# 5_Motors_MCU.net
KiCad netlist of a schematic drawn in Altium Designer
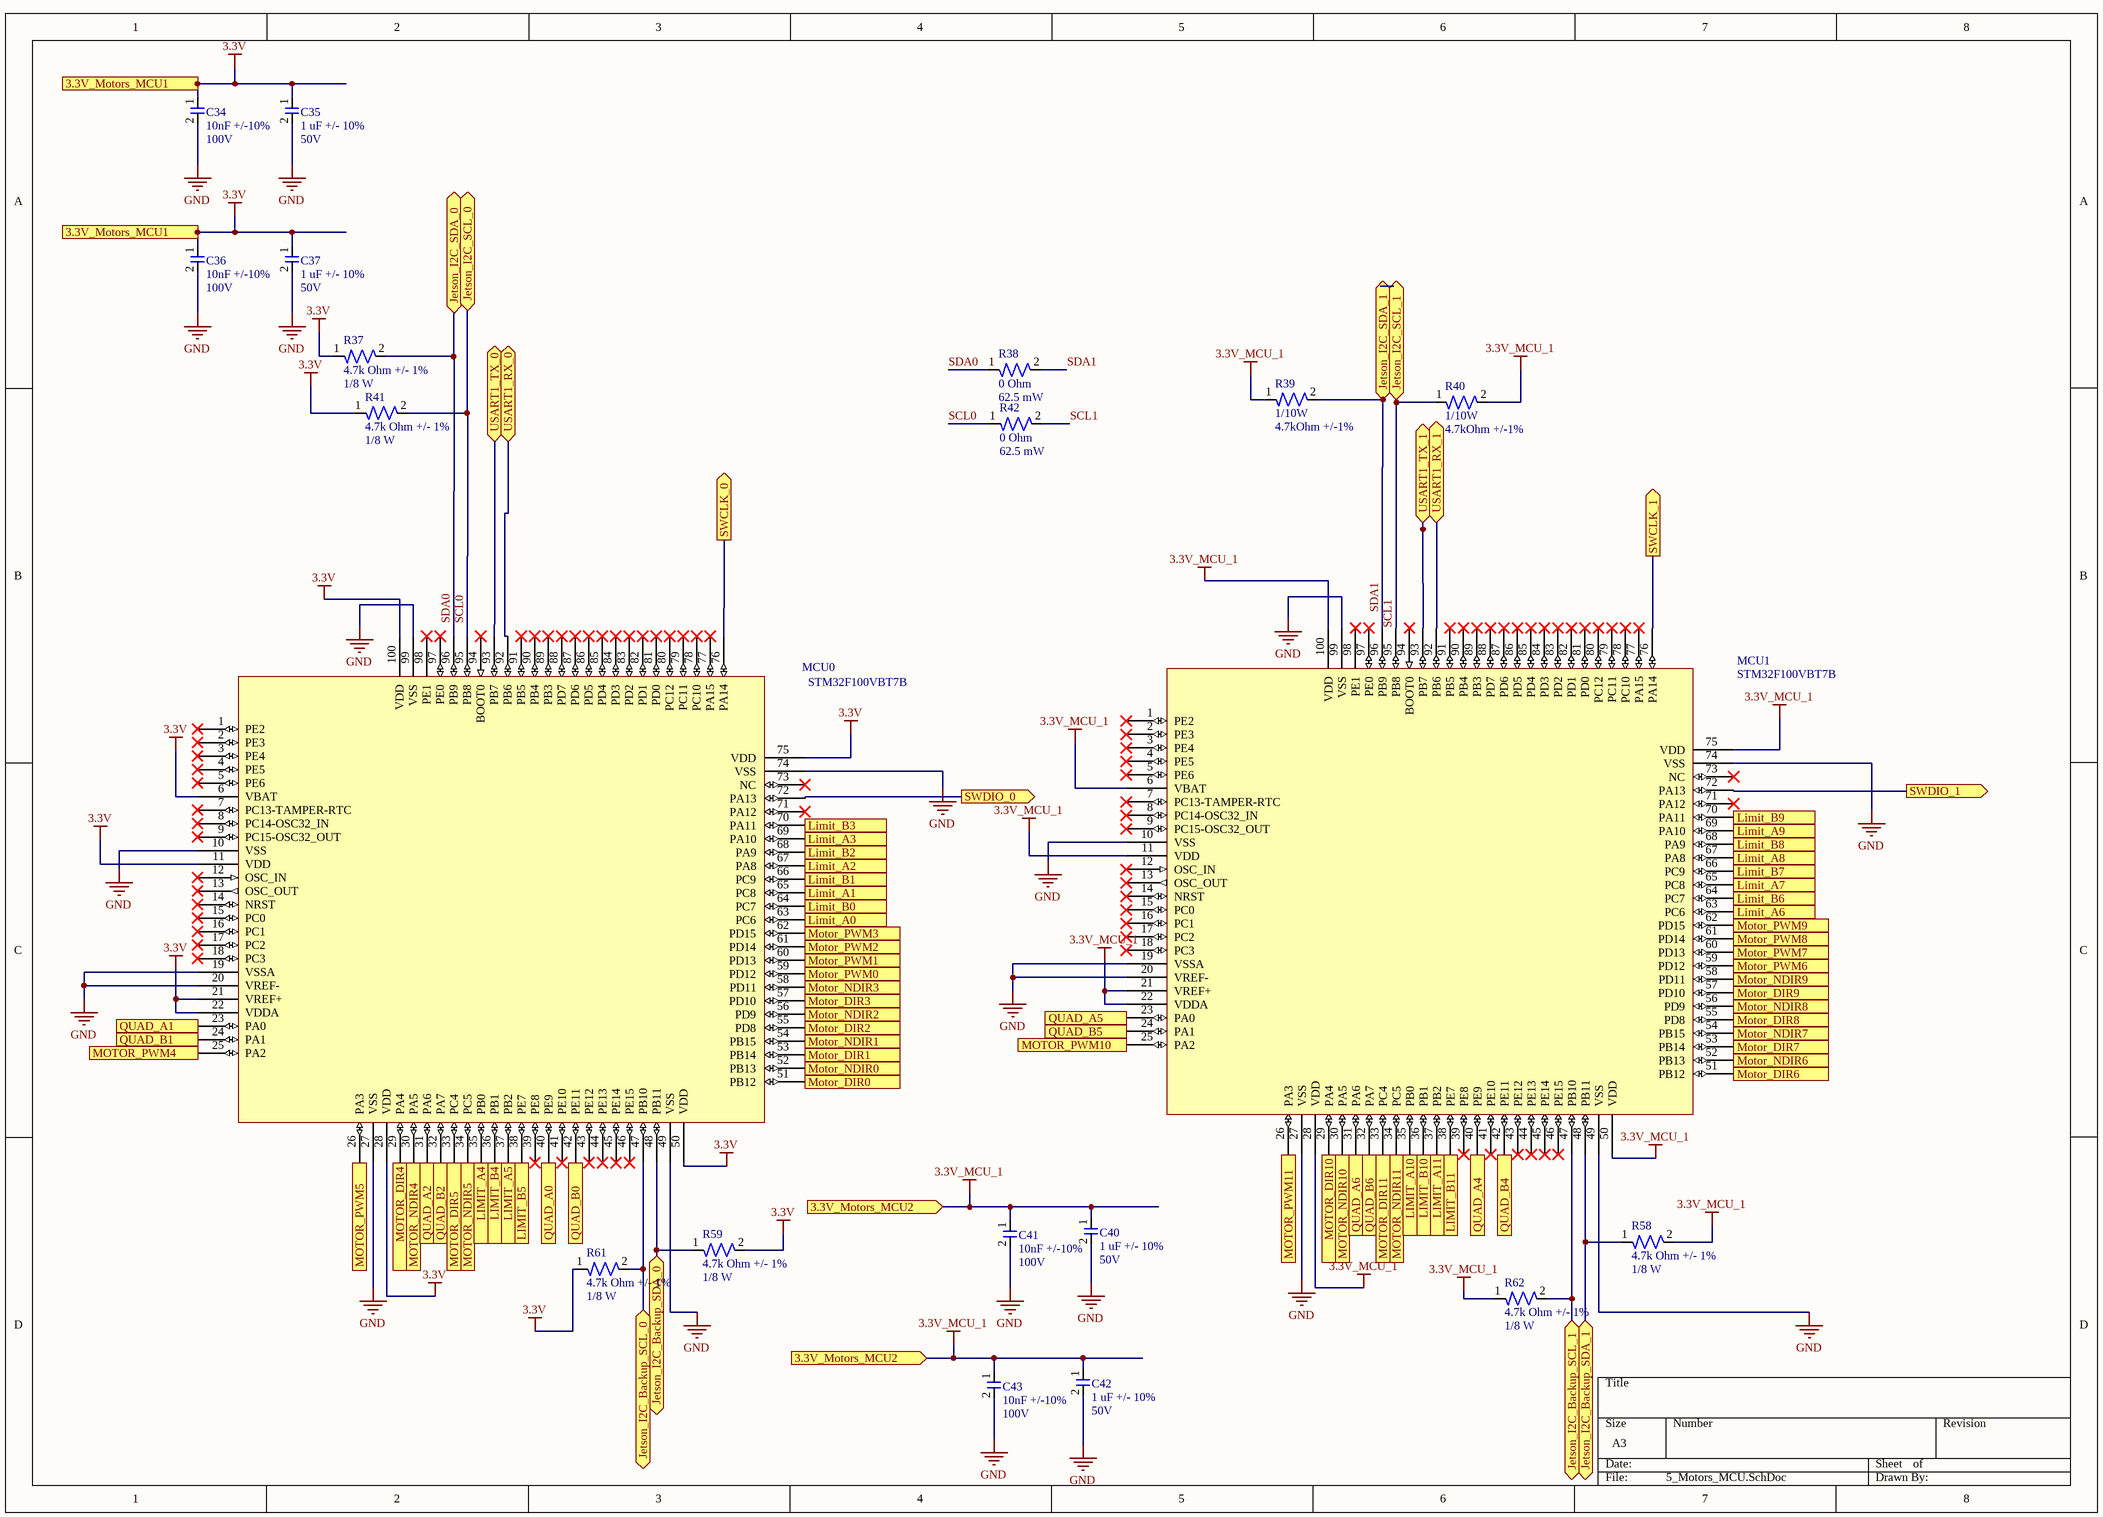
[diagram p0: 5_Motors_MCU.SchDoc]

(export (version "E")
  (design (tool "Eeschema 10.0.6"))
  (components
    (comp (ref "C34")
      (value "CC0603KRX7R0BB103")
      (footprint "CAP-0603")
      (description "100V 10nF X7R ±10% 0603 Multilayer Ceramic Capacitors MLCC - SMD/SMT ROHS")
      (fields
        (field (name "MANUFACTURER") "Yageo")
        (field (name "JLC PART NUMBER") "C107059")
        (field (name "CAPACITANCE") "10nF +/-10%")
        (field (name "VOLTAGE RATING") "100V")
      )
      (libsource (lib "MasterLib") (part "CAP-10N-0003-JLC"))
    )
    (comp (ref "C35")
      (value "GCM21BR71H105KA03L")
      (footprint "CAP-0805")
      (description "50V 1uF X7R ±10% 0805 Multilayer Ceramic Capacitors MLCC - SMD/SMT ROHS")
      (fields
        (field (name "JLC PART NUMBER") "C126592")
        (field (name "CAP") "1 uF +/- 10%")
        (field (name "VOLTAGE") "50V")
      )
      (libsource (lib "MasterLib") (part "CAP-1U-0003-JLC"))
    )
    (comp (ref "C36")
      (value "CC0603KRX7R0BB103")
      (footprint "CAP-0603")
      (description "100V 10nF X7R ±10% 0603 Multilayer Ceramic Capacitors MLCC - SMD/SMT ROHS")
      (fields
        (field (name "MANUFACTURER") "Yageo")
        (field (name "JLC PART NUMBER") "C107059")
        (field (name "CAPACITANCE") "10nF +/-10%")
        (field (name "VOLTAGE RATING") "100V")
      )
      (libsource (lib "MasterLib") (part "CAP-10N-0003-JLC"))
    )
    (comp (ref "C37")
      (value "GCM21BR71H105KA03L")
      (footprint "CAP-0805")
      (description "50V 1uF X7R ±10% 0805 Multilayer Ceramic Capacitors MLCC - SMD/SMT ROHS")
      (fields
        (field (name "JLC PART NUMBER") "C126592")
        (field (name "CAP") "1 uF +/- 10%")
        (field (name "VOLTAGE") "50V")
      )
      (libsource (lib "MasterLib") (part "CAP-1U-0003-JLC"))
    )
    (comp (ref "C40")
      (value "GCM21BR71H105KA03L")
      (footprint "CAP-0805")
      (description "50V 1uF X7R ±10% 0805 Multilayer Ceramic Capacitors MLCC - SMD/SMT ROHS")
      (fields
        (field (name "JLC PART NUMBER") "C126592")
        (field (name "CAP") "1 uF +/- 10%")
        (field (name "VOLTAGE") "50V")
      )
      (libsource (lib "MasterLib") (part "CAP-1U-0003-JLC"))
    )
    (comp (ref "C41")
      (value "CC0603KRX7R0BB103")
      (footprint "CAP-0603")
      (description "100V 10nF X7R ±10% 0603 Multilayer Ceramic Capacitors MLCC - SMD/SMT ROHS")
      (fields
        (field (name "MANUFACTURER") "Yageo")
        (field (name "JLC PART NUMBER") "C107059")
        (field (name "CAPACITANCE") "10nF +/-10%")
        (field (name "VOLTAGE RATING") "100V")
      )
      (libsource (lib "MasterLib") (part "CAP-10N-0003-JLC"))
    )
    (comp (ref "C42")
      (value "GCM21BR71H105KA03L")
      (footprint "CAP-0805")
      (description "50V 1uF X7R ±10% 0805 Multilayer Ceramic Capacitors MLCC - SMD/SMT ROHS")
      (fields
        (field (name "JLC PART NUMBER") "C126592")
        (field (name "CAP") "1 uF +/- 10%")
        (field (name "VOLTAGE") "50V")
      )
      (libsource (lib "MasterLib") (part "CAP-1U-0003-JLC"))
    )
    (comp (ref "C43")
      (value "CC0603KRX7R0BB103")
      (footprint "CAP-0603")
      (description "100V 10nF X7R ±10% 0603 Multilayer Ceramic Capacitors MLCC - SMD/SMT ROHS")
      (fields
        (field (name "MANUFACTURER") "Yageo")
        (field (name "JLC PART NUMBER") "C107059")
        (field (name "CAPACITANCE") "10nF +/-10%")
        (field (name "VOLTAGE RATING") "100V")
      )
      (libsource (lib "MasterLib") (part "CAP-10N-0003-JLC"))
    )
    (comp (ref "MCU0")
      (value "STM32F100VBT7B")
      (footprint "IC-STM32F100-0001")
      (libsource (lib "MasterLib") (part "IC-STM32F100-0001"))
    )
    (comp (ref "MCU1")
      (value "STM32F100VBT7B")
      (footprint "IC-STM32F100-0001")
      (libsource (lib "MasterLib") (part "IC-STM32F100-0001"))
    )
    (comp (ref "R37")
      (value "RC0402FR-7W4K7L")
      (footprint "RES-0402")
      (fields
        (field (name "RESISTANCE") "4.7k Ohm +/- 1%")
        (field (name "POWER") "1/8 W")
        (field (name "JLC PART NUMBER") "C606173")
      )
      (libsource (lib "MasterLib") (part "RES-4.7K-0003-JLC"))
    )
    (comp (ref "R38")
      (value "RC0402FR-070RL")
      (footprint "RES-0402")
      (description "62.5mW Thick Film Resistors 50V -55℃~+155℃ 0Ω 0402 Chip Resistor - Surface Mount ROHS")
      (fields
        (field (name "RESISTANCE") "0 Ohm")
        (field (name "POWER") "62.5 mW")
        (field (name "JLC PART NUMBER") "C106231")
      )
      (libsource (lib "MasterLib") (part "RES-0-0002-JLC"))
    )
    (comp (ref "R39")
      (value "AF0603FR-074K7L")
      (footprint "RES-0603")
      (description "RES SMD 4.7K OHM 1% 1/10W 0603")
      (fields
        (field (name "MANUFACTURER") "YAGEO")
        (field (name "POWER RATING") "1/10W")
        (field (name "RESISTANCE") "4.7kOhm +/-1%")
      )
      (libsource (lib "MasterLib") (part "RES-4.7K-0002"))
    )
    (comp (ref "R40")
      (value "AF0603FR-074K7L")
      (footprint "RES-0603")
      (description "RES SMD 4.7K OHM 1% 1/10W 0603")
      (fields
        (field (name "MANUFACTURER") "YAGEO")
        (field (name "POWER RATING") "1/10W")
        (field (name "RESISTANCE") "4.7kOhm +/-1%")
      )
      (libsource (lib "MasterLib") (part "RES-4.7K-0002"))
    )
    (comp (ref "R41")
      (value "RC0402FR-7W4K7L")
      (footprint "RES-0402")
      (fields
        (field (name "RESISTANCE") "4.7k Ohm +/- 1%")
        (field (name "POWER") "1/8 W")
        (field (name "JLC PART NUMBER") "C606173")
      )
      (libsource (lib "MasterLib") (part "RES-4.7K-0003-JLC"))
    )
    (comp (ref "R42")
      (value "RC0402FR-070RL")
      (footprint "RES-0402")
      (description "62.5mW Thick Film Resistors 50V -55℃~+155℃ 0Ω 0402 Chip Resistor - Surface Mount ROHS")
      (fields
        (field (name "RESISTANCE") "0 Ohm")
        (field (name "POWER") "62.5 mW")
        (field (name "JLC PART NUMBER") "C106231")
      )
      (libsource (lib "MasterLib") (part "RES-0-0002-JLC"))
    )
    (comp (ref "R58")
      (value "RC0402FR-7W4K7L")
      (footprint "RES-0402")
      (fields
        (field (name "RESISTANCE") "4.7k Ohm +/- 1%")
        (field (name "POWER") "1/8 W")
        (field (name "JLC PART NUMBER") "C606173")
      )
      (libsource (lib "MasterLib") (part "RES-4.7K-0003-JLC"))
    )
    (comp (ref "R59")
      (value "RC0402FR-7W4K7L")
      (footprint "RES-0402")
      (fields
        (field (name "RESISTANCE") "4.7k Ohm +/- 1%")
        (field (name "POWER") "1/8 W")
        (field (name "JLC PART NUMBER") "C606173")
      )
      (libsource (lib "MasterLib") (part "RES-4.7K-0003-JLC"))
    )
    (comp (ref "R61")
      (value "RC0402FR-7W4K7L")
      (footprint "RES-0402")
      (fields
        (field (name "RESISTANCE") "4.7k Ohm +/- 1%")
        (field (name "POWER") "1/8 W")
        (field (name "JLC PART NUMBER") "C606173")
      )
      (libsource (lib "MasterLib") (part "RES-4.7K-0003-JLC"))
    )
    (comp (ref "R62")
      (value "RC0402FR-7W4K7L")
      (footprint "RES-0402")
      (fields
        (field (name "RESISTANCE") "4.7k Ohm +/- 1%")
        (field (name "POWER") "1/8 W")
        (field (name "JLC PART NUMBER") "C606173")
      )
      (libsource (lib "MasterLib") (part "RES-4.7K-0003-JLC"))
    )
  )
  (nets
    (net (code "1") (name "/Jetson_I2C_Backup_SCL_0") (class "Default")
      (node (ref "MCU0") (pin "47") (pinfunction "PB10_47") (pintype "bidirectional"))
      (node (ref "R61") (pin "2") (pinfunction "2_2") (pintype "passive"))
    )
    (net (code "2") (name "/Jetson_I2C_Backup_SCL_1") (class "Default")
      (node (ref "MCU1") (pin "47") (pinfunction "PB10_47") (pintype "bidirectional"))
      (node (ref "R62") (pin "2") (pinfunction "2_2") (pintype "passive"))
    )
    (net (code "3") (name "/Jetson_I2C_Backup_SDA_0") (class "Default")
      (node (ref "MCU0") (pin "48") (pinfunction "PB11_48") (pintype "bidirectional"))
      (node (ref "R59") (pin "1") (pinfunction "1_1") (pintype "passive"))
    )
    (net (code "4") (name "/Jetson_I2C_Backup_SDA_1") (class "Default")
      (node (ref "MCU1") (pin "48") (pinfunction "PB11_48") (pintype "bidirectional"))
      (node (ref "R58") (pin "1") (pinfunction "1_1") (pintype "passive"))
    )
    (net (code "5") (name "/LIMIT_A4") (class "Default")
      (node (ref "MCU0") (pin "35") (pinfunction "PB0_35") (pintype "bidirectional"))
    )
    (net (code "6") (name "/LIMIT_A5") (class "Default")
      (node (ref "MCU0") (pin "37") (pinfunction "PB2_37") (pintype "bidirectional"))
    )
    (net (code "7") (name "/LIMIT_A10") (class "Default")
      (node (ref "MCU1") (pin "35") (pinfunction "PB0_35") (pintype "bidirectional"))
    )
    (net (code "8") (name "/LIMIT_A11") (class "Default")
      (node (ref "MCU1") (pin "37") (pinfunction "PB2_37") (pintype "bidirectional"))
    )
    (net (code "9") (name "/LIMIT_B4") (class "Default")
      (node (ref "MCU0") (pin "36") (pinfunction "PB1_36") (pintype "bidirectional"))
    )
    (net (code "10") (name "/LIMIT_B5") (class "Default")
      (node (ref "MCU0") (pin "38") (pinfunction "PE7_38") (pintype "bidirectional"))
    )
    (net (code "11") (name "/LIMIT_B10") (class "Default")
      (node (ref "MCU1") (pin "36") (pinfunction "PB1_36") (pintype "bidirectional"))
    )
    (net (code "12") (name "/LIMIT_B11") (class "Default")
      (node (ref "MCU1") (pin "38") (pinfunction "PE7_38") (pintype "bidirectional"))
    )
    (net (code "13") (name "/Limit_A0") (class "Default")
      (node (ref "MCU0") (pin "63") (pinfunction "PC6_63") (pintype "bidirectional"))
    )
    (net (code "14") (name "/Limit_A1") (class "Default")
      (node (ref "MCU0") (pin "65") (pinfunction "PC8_65") (pintype "bidirectional"))
    )
    (net (code "15") (name "/Limit_A2") (class "Default")
      (node (ref "MCU0") (pin "67") (pinfunction "PA8_67") (pintype "bidirectional"))
    )
    (net (code "16") (name "/Limit_A3") (class "Default")
      (node (ref "MCU0") (pin "69") (pinfunction "PA10_69") (pintype "bidirectional"))
    )
    (net (code "17") (name "/Limit_A6") (class "Default")
      (node (ref "MCU1") (pin "63") (pinfunction "PC6_63") (pintype "bidirectional"))
    )
    (net (code "18") (name "/Limit_A7") (class "Default")
      (node (ref "MCU1") (pin "65") (pinfunction "PC8_65") (pintype "bidirectional"))
    )
    (net (code "19") (name "/Limit_A8") (class "Default")
      (node (ref "MCU1") (pin "67") (pinfunction "PA8_67") (pintype "bidirectional"))
    )
    (net (code "20") (name "/Limit_A9") (class "Default")
      (node (ref "MCU1") (pin "69") (pinfunction "PA10_69") (pintype "bidirectional"))
    )
    (net (code "21") (name "/Limit_B0") (class "Default")
      (node (ref "MCU0") (pin "64") (pinfunction "PC7_64") (pintype "bidirectional"))
    )
    (net (code "22") (name "/Limit_B1") (class "Default")
      (node (ref "MCU0") (pin "66") (pinfunction "PC9_66") (pintype "bidirectional"))
    )
    (net (code "23") (name "/Limit_B2") (class "Default")
      (node (ref "MCU0") (pin "68") (pinfunction "PA9_68") (pintype "bidirectional"))
    )
    (net (code "24") (name "/Limit_B3") (class "Default")
      (node (ref "MCU0") (pin "70") (pinfunction "PA11_70") (pintype "bidirectional"))
    )
    (net (code "25") (name "/Limit_B6") (class "Default")
      (node (ref "MCU1") (pin "64") (pinfunction "PC7_64") (pintype "bidirectional"))
    )
    (net (code "26") (name "/Limit_B7") (class "Default")
      (node (ref "MCU1") (pin "66") (pinfunction "PC9_66") (pintype "bidirectional"))
    )
    (net (code "27") (name "/Limit_B8") (class "Default")
      (node (ref "MCU1") (pin "68") (pinfunction "PA9_68") (pintype "bidirectional"))
    )
    (net (code "28") (name "/Limit_B9") (class "Default")
      (node (ref "MCU1") (pin "70") (pinfunction "PA11_70") (pintype "bidirectional"))
    )
    (net (code "29") (name "/MOTOR_DIR4") (class "Default")
      (node (ref "MCU0") (pin "29") (pinfunction "PA4_29") (pintype "bidirectional"))
    )
    (net (code "30") (name "/MOTOR_DIR5") (class "Default")
      (node (ref "MCU0") (pin "33") (pinfunction "PC4_33") (pintype "bidirectional"))
    )
    (net (code "31") (name "/MOTOR_DIR10") (class "Default")
      (node (ref "MCU1") (pin "29") (pinfunction "PA4_29") (pintype "bidirectional"))
    )
    (net (code "32") (name "/MOTOR_DIR11") (class "Default")
      (node (ref "MCU1") (pin "33") (pinfunction "PC4_33") (pintype "bidirectional"))
    )
    (net (code "33") (name "/MOTOR_NDIR4") (class "Default")
      (node (ref "MCU0") (pin "30") (pinfunction "PA5_30") (pintype "bidirectional"))
    )
    (net (code "34") (name "/MOTOR_NDIR5") (class "Default")
      (node (ref "MCU0") (pin "34") (pinfunction "PC5_34") (pintype "bidirectional"))
    )
    (net (code "35") (name "/MOTOR_NDIR10") (class "Default")
      (node (ref "MCU1") (pin "30") (pinfunction "PA5_30") (pintype "bidirectional"))
    )
    (net (code "36") (name "/MOTOR_NDIR11") (class "Default")
      (node (ref "MCU1") (pin "34") (pinfunction "PC5_34") (pintype "bidirectional"))
    )
    (net (code "37") (name "/MOTOR_PWM4") (class "Default")
      (node (ref "MCU0") (pin "25") (pinfunction "PA2_25") (pintype "bidirectional"))
    )
    (net (code "38") (name "/MOTOR_PWM5") (class "Default")
      (node (ref "MCU0") (pin "26") (pinfunction "PA3_26") (pintype "bidirectional"))
    )
    (net (code "39") (name "/MOTOR_PWM10") (class "Default")
      (node (ref "MCU1") (pin "25") (pinfunction "PA2_25") (pintype "bidirectional"))
    )
    (net (code "40") (name "/MOTOR_PWM11") (class "Default")
      (node (ref "MCU1") (pin "26") (pinfunction "PA3_26") (pintype "bidirectional"))
    )
    (net (code "41") (name "/Motor_DIR0") (class "Default")
      (node (ref "MCU0") (pin "51") (pinfunction "PB12_51") (pintype "bidirectional"))
    )
    (net (code "42") (name "/Motor_DIR1") (class "Default")
      (node (ref "MCU0") (pin "53") (pinfunction "PB14_53") (pintype "bidirectional"))
    )
    (net (code "43") (name "/Motor_DIR2") (class "Default")
      (node (ref "MCU0") (pin "55") (pinfunction "PD8_55") (pintype "bidirectional"))
    )
    (net (code "44") (name "/Motor_DIR3") (class "Default")
      (node (ref "MCU0") (pin "57") (pinfunction "PD10_57") (pintype "bidirectional"))
    )
    (net (code "45") (name "/Motor_DIR6") (class "Default")
      (node (ref "MCU1") (pin "51") (pinfunction "PB12_51") (pintype "bidirectional"))
    )
    (net (code "46") (name "/Motor_DIR7") (class "Default")
      (node (ref "MCU1") (pin "53") (pinfunction "PB14_53") (pintype "bidirectional"))
    )
    (net (code "47") (name "/Motor_DIR8") (class "Default")
      (node (ref "MCU1") (pin "55") (pinfunction "PD8_55") (pintype "bidirectional"))
    )
    (net (code "48") (name "/Motor_DIR9") (class "Default")
      (node (ref "MCU1") (pin "57") (pinfunction "PD10_57") (pintype "bidirectional"))
    )
    (net (code "49") (name "/Motor_NDIR0") (class "Default")
      (node (ref "MCU0") (pin "52") (pinfunction "PB13_52") (pintype "bidirectional"))
    )
    (net (code "50") (name "/Motor_NDIR1") (class "Default")
      (node (ref "MCU0") (pin "54") (pinfunction "PB15_54") (pintype "bidirectional"))
    )
    (net (code "51") (name "/Motor_NDIR2") (class "Default")
      (node (ref "MCU0") (pin "56") (pinfunction "PD9_56") (pintype "bidirectional"))
    )
    (net (code "52") (name "/Motor_NDIR3") (class "Default")
      (node (ref "MCU0") (pin "58") (pinfunction "PD11_58") (pintype "bidirectional"))
    )
    (net (code "53") (name "/Motor_NDIR6") (class "Default")
      (node (ref "MCU1") (pin "52") (pinfunction "PB13_52") (pintype "bidirectional"))
    )
    (net (code "54") (name "/Motor_NDIR7") (class "Default")
      (node (ref "MCU1") (pin "54") (pinfunction "PB15_54") (pintype "bidirectional"))
    )
    (net (code "55") (name "/Motor_NDIR8") (class "Default")
      (node (ref "MCU1") (pin "56") (pinfunction "PD9_56") (pintype "bidirectional"))
    )
    (net (code "56") (name "/Motor_NDIR9") (class "Default")
      (node (ref "MCU1") (pin "58") (pinfunction "PD11_58") (pintype "bidirectional"))
    )
    (net (code "57") (name "/Motor_PWM0") (class "Default")
      (node (ref "MCU0") (pin "59") (pinfunction "PD12_59") (pintype "bidirectional"))
    )
    (net (code "58") (name "/Motor_PWM1") (class "Default")
      (node (ref "MCU0") (pin "60") (pinfunction "PD13_60") (pintype "bidirectional"))
    )
    (net (code "59") (name "/Motor_PWM2") (class "Default")
      (node (ref "MCU0") (pin "61") (pinfunction "PD14_61") (pintype "bidirectional"))
    )
    (net (code "60") (name "/Motor_PWM3") (class "Default")
      (node (ref "MCU0") (pin "62") (pinfunction "PD15_62") (pintype "bidirectional"))
    )
    (net (code "61") (name "/Motor_PWM6") (class "Default")
      (node (ref "MCU1") (pin "59") (pinfunction "PD12_59") (pintype "bidirectional"))
    )
    (net (code "62") (name "/Motor_PWM7") (class "Default")
      (node (ref "MCU1") (pin "60") (pinfunction "PD13_60") (pintype "bidirectional"))
    )
    (net (code "63") (name "/Motor_PWM8") (class "Default")
      (node (ref "MCU1") (pin "61") (pinfunction "PD14_61") (pintype "bidirectional"))
    )
    (net (code "64") (name "/Motor_PWM9") (class "Default")
      (node (ref "MCU1") (pin "62") (pinfunction "PD15_62") (pintype "bidirectional"))
    )
    (net (code "65") (name "/QUAD_A0") (class "Default")
      (node (ref "MCU0") (pin "40") (pinfunction "PE9_40") (pintype "bidirectional"))
    )
    (net (code "66") (name "/QUAD_A1") (class "Default")
      (node (ref "MCU0") (pin "23") (pinfunction "PA0_23") (pintype "bidirectional"))
    )
    (net (code "67") (name "/QUAD_A2") (class "Default")
      (node (ref "MCU0") (pin "31") (pinfunction "PA6_31") (pintype "bidirectional"))
    )
    (net (code "68") (name "/QUAD_A4") (class "Default")
      (node (ref "MCU1") (pin "40") (pinfunction "PE9_40") (pintype "bidirectional"))
    )
    (net (code "69") (name "/QUAD_A5") (class "Default")
      (node (ref "MCU1") (pin "23") (pinfunction "PA0_23") (pintype "bidirectional"))
    )
    (net (code "70") (name "/QUAD_A6") (class "Default")
      (node (ref "MCU1") (pin "31") (pinfunction "PA6_31") (pintype "bidirectional"))
    )
    (net (code "71") (name "/QUAD_B0") (class "Default")
      (node (ref "MCU0") (pin "42") (pinfunction "PE11_42") (pintype "bidirectional"))
    )
    (net (code "72") (name "/QUAD_B1") (class "Default")
      (node (ref "MCU0") (pin "24") (pinfunction "PA1_24") (pintype "bidirectional"))
    )
    (net (code "73") (name "/QUAD_B2") (class "Default")
      (node (ref "MCU0") (pin "32") (pinfunction "PA7_32") (pintype "bidirectional"))
    )
    (net (code "74") (name "/QUAD_B4") (class "Default")
      (node (ref "MCU1") (pin "42") (pinfunction "PE11_42") (pintype "bidirectional"))
    )
    (net (code "75") (name "/QUAD_B5") (class "Default")
      (node (ref "MCU1") (pin "24") (pinfunction "PA1_24") (pintype "bidirectional"))
    )
    (net (code "76") (name "/QUAD_B6") (class "Default")
      (node (ref "MCU1") (pin "32") (pinfunction "PA7_32") (pintype "bidirectional"))
    )
    (net (code "77") (name "/SCL0") (class "Default")
      (node (ref "MCU0") (pin "95") (pinfunction "PB8_95") (pintype "bidirectional"))
      (node (ref "R41") (pin "2") (pinfunction "2_2") (pintype "passive"))
      (node (ref "R42") (pin "1") (pinfunction "1_1") (pintype "passive"))
    )
    (net (code "78") (name "/SCL1") (class "Default")
      (node (ref "MCU1") (pin "95") (pinfunction "PB8_95") (pintype "bidirectional"))
      (node (ref "R40") (pin "1") (pinfunction "1_1") (pintype "passive"))
      (node (ref "R42") (pin "2") (pinfunction "2_2") (pintype "passive"))
    )
    (net (code "79") (name "/SDA0") (class "Default")
      (node (ref "MCU0") (pin "96") (pinfunction "PB9_96") (pintype "bidirectional"))
      (node (ref "R37") (pin "2") (pinfunction "2_2") (pintype "passive"))
      (node (ref "R38") (pin "1") (pinfunction "1_1") (pintype "passive"))
    )
    (net (code "80") (name "/SDA1") (class "Default")
      (node (ref "MCU1") (pin "96") (pinfunction "PB9_96") (pintype "bidirectional"))
      (node (ref "R38") (pin "2") (pinfunction "2_2") (pintype "passive"))
      (node (ref "R39") (pin "2") (pinfunction "2_2") (pintype "passive"))
    )
    (net (code "81") (name "/SWCLK_0") (class "Default")
      (node (ref "MCU0") (pin "76") (pinfunction "PA14_76") (pintype "bidirectional"))
    )
    (net (code "82") (name "/SWCLK_1") (class "Default")
      (node (ref "MCU1") (pin "76") (pinfunction "PA14_76") (pintype "bidirectional"))
    )
    (net (code "83") (name "/SWDIO_0") (class "Default")
      (node (ref "MCU0") (pin "72") (pinfunction "PA13_72") (pintype "bidirectional"))
    )
    (net (code "84") (name "/SWDIO_1") (class "Default")
      (node (ref "MCU1") (pin "72") (pinfunction "PA13_72") (pintype "bidirectional"))
    )
    (net (code "85") (name "/USART1_RX_0") (class "Default")
      (node (ref "MCU0") (pin "92") (pinfunction "PB6_92") (pintype "bidirectional"))
    )
    (net (code "86") (name "/USART1_RX_1") (class "Default")
      (node (ref "MCU1") (pin "92") (pinfunction "PB6_92") (pintype "bidirectional"))
    )
    (net (code "87") (name "/USART1_TX_0") (class "Default")
      (node (ref "MCU0") (pin "93") (pinfunction "PB7_93") (pintype "bidirectional"))
    )
    (net (code "88") (name "/USART1_TX_1") (class "Default")
      (node (ref "MCU1") (pin "93") (pinfunction "PB7_93") (pintype "bidirectional"))
    )
    (net (code "89") (name "3.3V") (class "Default")
      (node (ref "C34") (pin "1") (pinfunction "1_1") (pintype "passive"))
      (node (ref "C35") (pin "1") (pinfunction "1_1") (pintype "passive"))
      (node (ref "C36") (pin "1") (pinfunction "1_1") (pintype "passive"))
      (node (ref "C37") (pin "1") (pinfunction "1_1") (pintype "passive"))
      (node (ref "MCU0") (pin "100") (pinfunction "VDD_100") (pintype "power_in"))
      (node (ref "MCU0") (pin "11") (pinfunction "VDD_11") (pintype "power_in"))
      (node (ref "MCU0") (pin "21") (pinfunction "VREF+_21") (pintype "power_in"))
      (node (ref "MCU0") (pin "22") (pinfunction "VDDA_22") (pintype "power_in"))
      (node (ref "MCU0") (pin "28") (pinfunction "VDD_28") (pintype "power_in"))
      (node (ref "MCU0") (pin "50") (pinfunction "VDD_50") (pintype "power_in"))
      (node (ref "MCU0") (pin "6") (pinfunction "VBAT_6") (pintype "power_in"))
      (node (ref "MCU0") (pin "75") (pinfunction "VDD_75") (pintype "power_in"))
      (node (ref "R37") (pin "1") (pinfunction "1_1") (pintype "passive"))
      (node (ref "R41") (pin "1") (pinfunction "1_1") (pintype "passive"))
      (node (ref "R59") (pin "2") (pinfunction "2_2") (pintype "passive"))
      (node (ref "R61") (pin "1") (pinfunction "1_1") (pintype "passive"))
    )
    (net (code "90") (name "3.3V_MCU_1") (class "Default")
      (node (ref "C40") (pin "1") (pinfunction "1_1") (pintype "passive"))
      (node (ref "C41") (pin "1") (pinfunction "1_1") (pintype "passive"))
      (node (ref "C42") (pin "1") (pinfunction "1_1") (pintype "passive"))
      (node (ref "C43") (pin "1") (pinfunction "1_1") (pintype "passive"))
      (node (ref "MCU1") (pin "100") (pinfunction "VDD_100") (pintype "power_in"))
      (node (ref "MCU1") (pin "11") (pinfunction "VDD_11") (pintype "power_in"))
      (node (ref "MCU1") (pin "21") (pinfunction "VREF+_21") (pintype "power_in"))
      (node (ref "MCU1") (pin "22") (pinfunction "VDDA_22") (pintype "power_in"))
      (node (ref "MCU1") (pin "28") (pinfunction "VDD_28") (pintype "power_in"))
      (node (ref "MCU1") (pin "50") (pinfunction "VDD_50") (pintype "power_in"))
      (node (ref "MCU1") (pin "6") (pinfunction "VBAT_6") (pintype "power_in"))
      (node (ref "MCU1") (pin "75") (pinfunction "VDD_75") (pintype "power_in"))
      (node (ref "R39") (pin "1") (pinfunction "1_1") (pintype "passive"))
      (node (ref "R40") (pin "2") (pinfunction "2_2") (pintype "passive"))
      (node (ref "R58") (pin "2") (pinfunction "2_2") (pintype "passive"))
      (node (ref "R62") (pin "1") (pinfunction "1_1") (pintype "passive"))
    )
    (net (code "91") (name "GND") (class "Default")
      (node (ref "C34") (pin "2") (pinfunction "2_2") (pintype "passive"))
      (node (ref "C35") (pin "2") (pinfunction "2_2") (pintype "passive"))
      (node (ref "C36") (pin "2") (pinfunction "2_2") (pintype "passive"))
      (node (ref "C37") (pin "2") (pinfunction "2_2") (pintype "passive"))
      (node (ref "C40") (pin "2") (pinfunction "2_2") (pintype "passive"))
      (node (ref "C41") (pin "2") (pinfunction "2_2") (pintype "passive"))
      (node (ref "C42") (pin "2") (pinfunction "2_2") (pintype "passive"))
      (node (ref "C43") (pin "2") (pinfunction "2_2") (pintype "passive"))
      (node (ref "MCU0") (pin "10") (pinfunction "VSS_10") (pintype "power_in"))
      (node (ref "MCU0") (pin "19") (pinfunction "VSSA_19") (pintype "power_in"))
      (node (ref "MCU0") (pin "20") (pinfunction "VREF-_20") (pintype "power_in"))
      (node (ref "MCU0") (pin "27") (pinfunction "VSS_27") (pintype "power_in"))
      (node (ref "MCU0") (pin "49") (pinfunction "VSS_49") (pintype "power_in"))
      (node (ref "MCU0") (pin "74") (pinfunction "VSS_74") (pintype "power_in"))
      (node (ref "MCU0") (pin "99") (pinfunction "VSS_99") (pintype "power_in"))
      (node (ref "MCU1") (pin "10") (pinfunction "VSS_10") (pintype "power_in"))
      (node (ref "MCU1") (pin "19") (pinfunction "VSSA_19") (pintype "power_in"))
      (node (ref "MCU1") (pin "20") (pinfunction "VREF-_20") (pintype "power_in"))
      (node (ref "MCU1") (pin "27") (pinfunction "VSS_27") (pintype "power_in"))
      (node (ref "MCU1") (pin "49") (pinfunction "VSS_49") (pintype "power_in"))
      (node (ref "MCU1") (pin "74") (pinfunction "VSS_74") (pintype "power_in"))
      (node (ref "MCU1") (pin "99") (pinfunction "VSS_99") (pintype "power_in"))
    )
    (net (code "92") (name "unconnected-(MCU0-BOOT0-Pad94)") (class "Default")
      (node (ref "MCU0") (pin "94") (pinfunction "BOOT0_94") (pintype "input+no_connect"))
    )
    (net (code "93") (name "unconnected-(MCU0-NC-Pad73)") (class "Default")
      (node (ref "MCU0") (pin "73") (pinfunction "NC_73") (pintype "bidirectional+no_connect"))
    )
    (net (code "94") (name "unconnected-(MCU0-NRST-Pad14)") (class "Default")
      (node (ref "MCU0") (pin "14") (pinfunction "NRST_14") (pintype "bidirectional+no_connect"))
    )
    (net (code "95") (name "unconnected-(MCU0-OSC_IN-Pad12)") (class "Default")
      (node (ref "MCU0") (pin "12") (pinfunction "OSC_IN_12") (pintype "input+no_connect"))
    )
    (net (code "96") (name "unconnected-(MCU0-OSC_OUT-Pad13)") (class "Default")
      (node (ref "MCU0") (pin "13") (pinfunction "OSC_OUT_13") (pintype "output+no_connect"))
    )
    (net (code "97") (name "unconnected-(MCU0-PA12-Pad71)") (class "Default")
      (node (ref "MCU0") (pin "71") (pinfunction "PA12_71") (pintype "bidirectional+no_connect"))
    )
    (net (code "98") (name "unconnected-(MCU0-PA15-Pad77)") (class "Default")
      (node (ref "MCU0") (pin "77") (pinfunction "PA15_77") (pintype "bidirectional+no_connect"))
    )
    (net (code "99") (name "unconnected-(MCU0-PB3-Pad89)") (class "Default")
      (node (ref "MCU0") (pin "89") (pinfunction "PB3_89") (pintype "bidirectional+no_connect"))
    )
    (net (code "100") (name "unconnected-(MCU0-PB4-Pad90)") (class "Default")
      (node (ref "MCU0") (pin "90") (pinfunction "PB4_90") (pintype "bidirectional+no_connect"))
    )
    (net (code "101") (name "unconnected-(MCU0-PB5-Pad91)") (class "Default")
      (node (ref "MCU0") (pin "91") (pinfunction "PB5_91") (pintype "bidirectional+no_connect"))
    )
    (net (code "102") (name "unconnected-(MCU0-PC0-Pad15)") (class "Default")
      (node (ref "MCU0") (pin "15") (pinfunction "PC0_15") (pintype "bidirectional+no_connect"))
    )
    (net (code "103") (name "unconnected-(MCU0-PC1-Pad16)") (class "Default")
      (node (ref "MCU0") (pin "16") (pinfunction "PC1_16") (pintype "bidirectional+no_connect"))
    )
    (net (code "104") (name "unconnected-(MCU0-PC2-Pad17)") (class "Default")
      (node (ref "MCU0") (pin "17") (pinfunction "PC2_17") (pintype "bidirectional+no_connect"))
    )
    (net (code "105") (name "unconnected-(MCU0-PC3-Pad18)") (class "Default")
      (node (ref "MCU0") (pin "18") (pinfunction "PC3_18") (pintype "bidirectional+no_connect"))
    )
    (net (code "106") (name "unconnected-(MCU0-PC10-Pad78)") (class "Default")
      (node (ref "MCU0") (pin "78") (pinfunction "PC10_78") (pintype "bidirectional+no_connect"))
    )
    (net (code "107") (name "unconnected-(MCU0-PC11-Pad79)") (class "Default")
      (node (ref "MCU0") (pin "79") (pinfunction "PC11_79") (pintype "bidirectional+no_connect"))
    )
    (net (code "108") (name "unconnected-(MCU0-PC12-Pad80)") (class "Default")
      (node (ref "MCU0") (pin "80") (pinfunction "PC12_80") (pintype "bidirectional+no_connect"))
    )
    (net (code "109") (name "unconnected-(MCU0-PC13-TAMPER-RTC-Pad7)") (class "Default")
      (node (ref "MCU0") (pin "7") (pinfunction "PC13-TAMPER-RTC_7") (pintype "bidirectional+no_connect"))
    )
    (net (code "110") (name "unconnected-(MCU0-PC14-OSC32_IN-Pad8)") (class "Default")
      (node (ref "MCU0") (pin "8") (pinfunction "PC14-OSC32_IN_8") (pintype "bidirectional+no_connect"))
    )
    (net (code "111") (name "unconnected-(MCU0-PC15-OSC32_OUT-Pad9)") (class "Default")
      (node (ref "MCU0") (pin "9") (pinfunction "PC15-OSC32_OUT_9") (pintype "bidirectional+no_connect"))
    )
    (net (code "112") (name "unconnected-(MCU0-PD0-Pad81)") (class "Default")
      (node (ref "MCU0") (pin "81") (pinfunction "PD0_81") (pintype "bidirectional+no_connect"))
    )
    (net (code "113") (name "unconnected-(MCU0-PD1-Pad82)") (class "Default")
      (node (ref "MCU0") (pin "82") (pinfunction "PD1_82") (pintype "bidirectional+no_connect"))
    )
    (net (code "114") (name "unconnected-(MCU0-PD2-Pad83)") (class "Default")
      (node (ref "MCU0") (pin "83") (pinfunction "PD2_83") (pintype "bidirectional+no_connect"))
    )
    (net (code "115") (name "unconnected-(MCU0-PD3-Pad84)") (class "Default")
      (node (ref "MCU0") (pin "84") (pinfunction "PD3_84") (pintype "bidirectional+no_connect"))
    )
    (net (code "116") (name "unconnected-(MCU0-PD4-Pad85)") (class "Default")
      (node (ref "MCU0") (pin "85") (pinfunction "PD4_85") (pintype "bidirectional+no_connect"))
    )
    (net (code "117") (name "unconnected-(MCU0-PD5-Pad86)") (class "Default")
      (node (ref "MCU0") (pin "86") (pinfunction "PD5_86") (pintype "bidirectional+no_connect"))
    )
    (net (code "118") (name "unconnected-(MCU0-PD6-Pad87)") (class "Default")
      (node (ref "MCU0") (pin "87") (pinfunction "PD6_87") (pintype "bidirectional+no_connect"))
    )
    (net (code "119") (name "unconnected-(MCU0-PD7-Pad88)") (class "Default")
      (node (ref "MCU0") (pin "88") (pinfunction "PD7_88") (pintype "bidirectional+no_connect"))
    )
    (net (code "120") (name "unconnected-(MCU0-PE0-Pad97)") (class "Default")
      (node (ref "MCU0") (pin "97") (pinfunction "PE0_97") (pintype "bidirectional+no_connect"))
    )
    (net (code "121") (name "unconnected-(MCU0-PE1-Pad98)") (class "Default")
      (node (ref "MCU0") (pin "98") (pinfunction "PE1_98") (pintype "power_in+no_connect"))
    )
    (net (code "122") (name "unconnected-(MCU0-PE2-Pad1)") (class "Default")
      (node (ref "MCU0") (pin "1") (pinfunction "PE2_1") (pintype "bidirectional+no_connect"))
    )
    (net (code "123") (name "unconnected-(MCU0-PE3-Pad2)") (class "Default")
      (node (ref "MCU0") (pin "2") (pinfunction "PE3_2") (pintype "bidirectional+no_connect"))
    )
    (net (code "124") (name "unconnected-(MCU0-PE4-Pad3)") (class "Default")
      (node (ref "MCU0") (pin "3") (pinfunction "PE4_3") (pintype "bidirectional+no_connect"))
    )
    (net (code "125") (name "unconnected-(MCU0-PE5-Pad4)") (class "Default")
      (node (ref "MCU0") (pin "4") (pinfunction "PE5_4") (pintype "bidirectional+no_connect"))
    )
    (net (code "126") (name "unconnected-(MCU0-PE6-Pad5)") (class "Default")
      (node (ref "MCU0") (pin "5") (pinfunction "PE6_5") (pintype "bidirectional+no_connect"))
    )
    (net (code "127") (name "unconnected-(MCU0-PE8-Pad39)") (class "Default")
      (node (ref "MCU0") (pin "39") (pinfunction "PE8_39") (pintype "bidirectional+no_connect"))
    )
    (net (code "128") (name "unconnected-(MCU0-PE10-Pad41)") (class "Default")
      (node (ref "MCU0") (pin "41") (pinfunction "PE10_41") (pintype "bidirectional+no_connect"))
    )
    (net (code "129") (name "unconnected-(MCU0-PE12-Pad43)") (class "Default")
      (node (ref "MCU0") (pin "43") (pinfunction "PE12_43") (pintype "bidirectional+no_connect"))
    )
    (net (code "130") (name "unconnected-(MCU0-PE13-Pad44)") (class "Default")
      (node (ref "MCU0") (pin "44") (pinfunction "PE13_44") (pintype "bidirectional+no_connect"))
    )
    (net (code "131") (name "unconnected-(MCU0-PE14-Pad45)") (class "Default")
      (node (ref "MCU0") (pin "45") (pinfunction "PE14_45") (pintype "bidirectional+no_connect"))
    )
    (net (code "132") (name "unconnected-(MCU0-PE15-Pad46)") (class "Default")
      (node (ref "MCU0") (pin "46") (pinfunction "PE15_46") (pintype "bidirectional+no_connect"))
    )
    (net (code "133") (name "unconnected-(MCU1-BOOT0-Pad94)") (class "Default")
      (node (ref "MCU1") (pin "94") (pinfunction "BOOT0_94") (pintype "input+no_connect"))
    )
    (net (code "134") (name "unconnected-(MCU1-NC-Pad73)") (class "Default")
      (node (ref "MCU1") (pin "73") (pinfunction "NC_73") (pintype "bidirectional+no_connect"))
    )
    (net (code "135") (name "unconnected-(MCU1-NRST-Pad14)") (class "Default")
      (node (ref "MCU1") (pin "14") (pinfunction "NRST_14") (pintype "bidirectional+no_connect"))
    )
    (net (code "136") (name "unconnected-(MCU1-OSC_IN-Pad12)") (class "Default")
      (node (ref "MCU1") (pin "12") (pinfunction "OSC_IN_12") (pintype "input+no_connect"))
    )
    (net (code "137") (name "unconnected-(MCU1-OSC_OUT-Pad13)") (class "Default")
      (node (ref "MCU1") (pin "13") (pinfunction "OSC_OUT_13") (pintype "output+no_connect"))
    )
    (net (code "138") (name "unconnected-(MCU1-PA12-Pad71)") (class "Default")
      (node (ref "MCU1") (pin "71") (pinfunction "PA12_71") (pintype "bidirectional+no_connect"))
    )
    (net (code "139") (name "unconnected-(MCU1-PA15-Pad77)") (class "Default")
      (node (ref "MCU1") (pin "77") (pinfunction "PA15_77") (pintype "bidirectional+no_connect"))
    )
    (net (code "140") (name "unconnected-(MCU1-PB3-Pad89)") (class "Default")
      (node (ref "MCU1") (pin "89") (pinfunction "PB3_89") (pintype "bidirectional+no_connect"))
    )
    (net (code "141") (name "unconnected-(MCU1-PB4-Pad90)") (class "Default")
      (node (ref "MCU1") (pin "90") (pinfunction "PB4_90") (pintype "bidirectional+no_connect"))
    )
    (net (code "142") (name "unconnected-(MCU1-PB5-Pad91)") (class "Default")
      (node (ref "MCU1") (pin "91") (pinfunction "PB5_91") (pintype "bidirectional+no_connect"))
    )
    (net (code "143") (name "unconnected-(MCU1-PC0-Pad15)") (class "Default")
      (node (ref "MCU1") (pin "15") (pinfunction "PC0_15") (pintype "bidirectional+no_connect"))
    )
    (net (code "144") (name "unconnected-(MCU1-PC1-Pad16)") (class "Default")
      (node (ref "MCU1") (pin "16") (pinfunction "PC1_16") (pintype "bidirectional+no_connect"))
    )
    (net (code "145") (name "unconnected-(MCU1-PC2-Pad17)") (class "Default")
      (node (ref "MCU1") (pin "17") (pinfunction "PC2_17") (pintype "bidirectional+no_connect"))
    )
    (net (code "146") (name "unconnected-(MCU1-PC3-Pad18)") (class "Default")
      (node (ref "MCU1") (pin "18") (pinfunction "PC3_18") (pintype "bidirectional+no_connect"))
    )
    (net (code "147") (name "unconnected-(MCU1-PC10-Pad78)") (class "Default")
      (node (ref "MCU1") (pin "78") (pinfunction "PC10_78") (pintype "bidirectional+no_connect"))
    )
    (net (code "148") (name "unconnected-(MCU1-PC11-Pad79)") (class "Default")
      (node (ref "MCU1") (pin "79") (pinfunction "PC11_79") (pintype "bidirectional+no_connect"))
    )
    (net (code "149") (name "unconnected-(MCU1-PC12-Pad80)") (class "Default")
      (node (ref "MCU1") (pin "80") (pinfunction "PC12_80") (pintype "bidirectional+no_connect"))
    )
    (net (code "150") (name "unconnected-(MCU1-PC13-TAMPER-RTC-Pad7)") (class "Default")
      (node (ref "MCU1") (pin "7") (pinfunction "PC13-TAMPER-RTC_7") (pintype "bidirectional+no_connect"))
    )
    (net (code "151") (name "unconnected-(MCU1-PC14-OSC32_IN-Pad8)") (class "Default")
      (node (ref "MCU1") (pin "8") (pinfunction "PC14-OSC32_IN_8") (pintype "bidirectional+no_connect"))
    )
    (net (code "152") (name "unconnected-(MCU1-PC15-OSC32_OUT-Pad9)") (class "Default")
      (node (ref "MCU1") (pin "9") (pinfunction "PC15-OSC32_OUT_9") (pintype "bidirectional+no_connect"))
    )
    (net (code "153") (name "unconnected-(MCU1-PD0-Pad81)") (class "Default")
      (node (ref "MCU1") (pin "81") (pinfunction "PD0_81") (pintype "bidirectional+no_connect"))
    )
    (net (code "154") (name "unconnected-(MCU1-PD1-Pad82)") (class "Default")
      (node (ref "MCU1") (pin "82") (pinfunction "PD1_82") (pintype "bidirectional+no_connect"))
    )
    (net (code "155") (name "unconnected-(MCU1-PD2-Pad83)") (class "Default")
      (node (ref "MCU1") (pin "83") (pinfunction "PD2_83") (pintype "bidirectional+no_connect"))
    )
    (net (code "156") (name "unconnected-(MCU1-PD3-Pad84)") (class "Default")
      (node (ref "MCU1") (pin "84") (pinfunction "PD3_84") (pintype "bidirectional+no_connect"))
    )
    (net (code "157") (name "unconnected-(MCU1-PD4-Pad85)") (class "Default")
      (node (ref "MCU1") (pin "85") (pinfunction "PD4_85") (pintype "bidirectional+no_connect"))
    )
    (net (code "158") (name "unconnected-(MCU1-PD5-Pad86)") (class "Default")
      (node (ref "MCU1") (pin "86") (pinfunction "PD5_86") (pintype "bidirectional+no_connect"))
    )
    (net (code "159") (name "unconnected-(MCU1-PD6-Pad87)") (class "Default")
      (node (ref "MCU1") (pin "87") (pinfunction "PD6_87") (pintype "bidirectional+no_connect"))
    )
    (net (code "160") (name "unconnected-(MCU1-PD7-Pad88)") (class "Default")
      (node (ref "MCU1") (pin "88") (pinfunction "PD7_88") (pintype "bidirectional+no_connect"))
    )
    (net (code "161") (name "unconnected-(MCU1-PE0-Pad97)") (class "Default")
      (node (ref "MCU1") (pin "97") (pinfunction "PE0_97") (pintype "bidirectional+no_connect"))
    )
    (net (code "162") (name "unconnected-(MCU1-PE1-Pad98)") (class "Default")
      (node (ref "MCU1") (pin "98") (pinfunction "PE1_98") (pintype "power_in+no_connect"))
    )
    (net (code "163") (name "unconnected-(MCU1-PE2-Pad1)") (class "Default")
      (node (ref "MCU1") (pin "1") (pinfunction "PE2_1") (pintype "bidirectional+no_connect"))
    )
    (net (code "164") (name "unconnected-(MCU1-PE3-Pad2)") (class "Default")
      (node (ref "MCU1") (pin "2") (pinfunction "PE3_2") (pintype "bidirectional+no_connect"))
    )
    (net (code "165") (name "unconnected-(MCU1-PE4-Pad3)") (class "Default")
      (node (ref "MCU1") (pin "3") (pinfunction "PE4_3") (pintype "bidirectional+no_connect"))
    )
    (net (code "166") (name "unconnected-(MCU1-PE5-Pad4)") (class "Default")
      (node (ref "MCU1") (pin "4") (pinfunction "PE5_4") (pintype "bidirectional+no_connect"))
    )
    (net (code "167") (name "unconnected-(MCU1-PE6-Pad5)") (class "Default")
      (node (ref "MCU1") (pin "5") (pinfunction "PE6_5") (pintype "bidirectional+no_connect"))
    )
    (net (code "168") (name "unconnected-(MCU1-PE8-Pad39)") (class "Default")
      (node (ref "MCU1") (pin "39") (pinfunction "PE8_39") (pintype "bidirectional+no_connect"))
    )
    (net (code "169") (name "unconnected-(MCU1-PE10-Pad41)") (class "Default")
      (node (ref "MCU1") (pin "41") (pinfunction "PE10_41") (pintype "bidirectional+no_connect"))
    )
    (net (code "170") (name "unconnected-(MCU1-PE12-Pad43)") (class "Default")
      (node (ref "MCU1") (pin "43") (pinfunction "PE12_43") (pintype "bidirectional+no_connect"))
    )
    (net (code "171") (name "unconnected-(MCU1-PE13-Pad44)") (class "Default")
      (node (ref "MCU1") (pin "44") (pinfunction "PE13_44") (pintype "bidirectional+no_connect"))
    )
    (net (code "172") (name "unconnected-(MCU1-PE14-Pad45)") (class "Default")
      (node (ref "MCU1") (pin "45") (pinfunction "PE14_45") (pintype "bidirectional+no_connect"))
    )
    (net (code "173") (name "unconnected-(MCU1-PE15-Pad46)") (class "Default")
      (node (ref "MCU1") (pin "46") (pinfunction "PE15_46") (pintype "bidirectional+no_connect"))
    )
  )
)
